# radio.net
KiCad netlist of a schematic drawn in Altium Designer
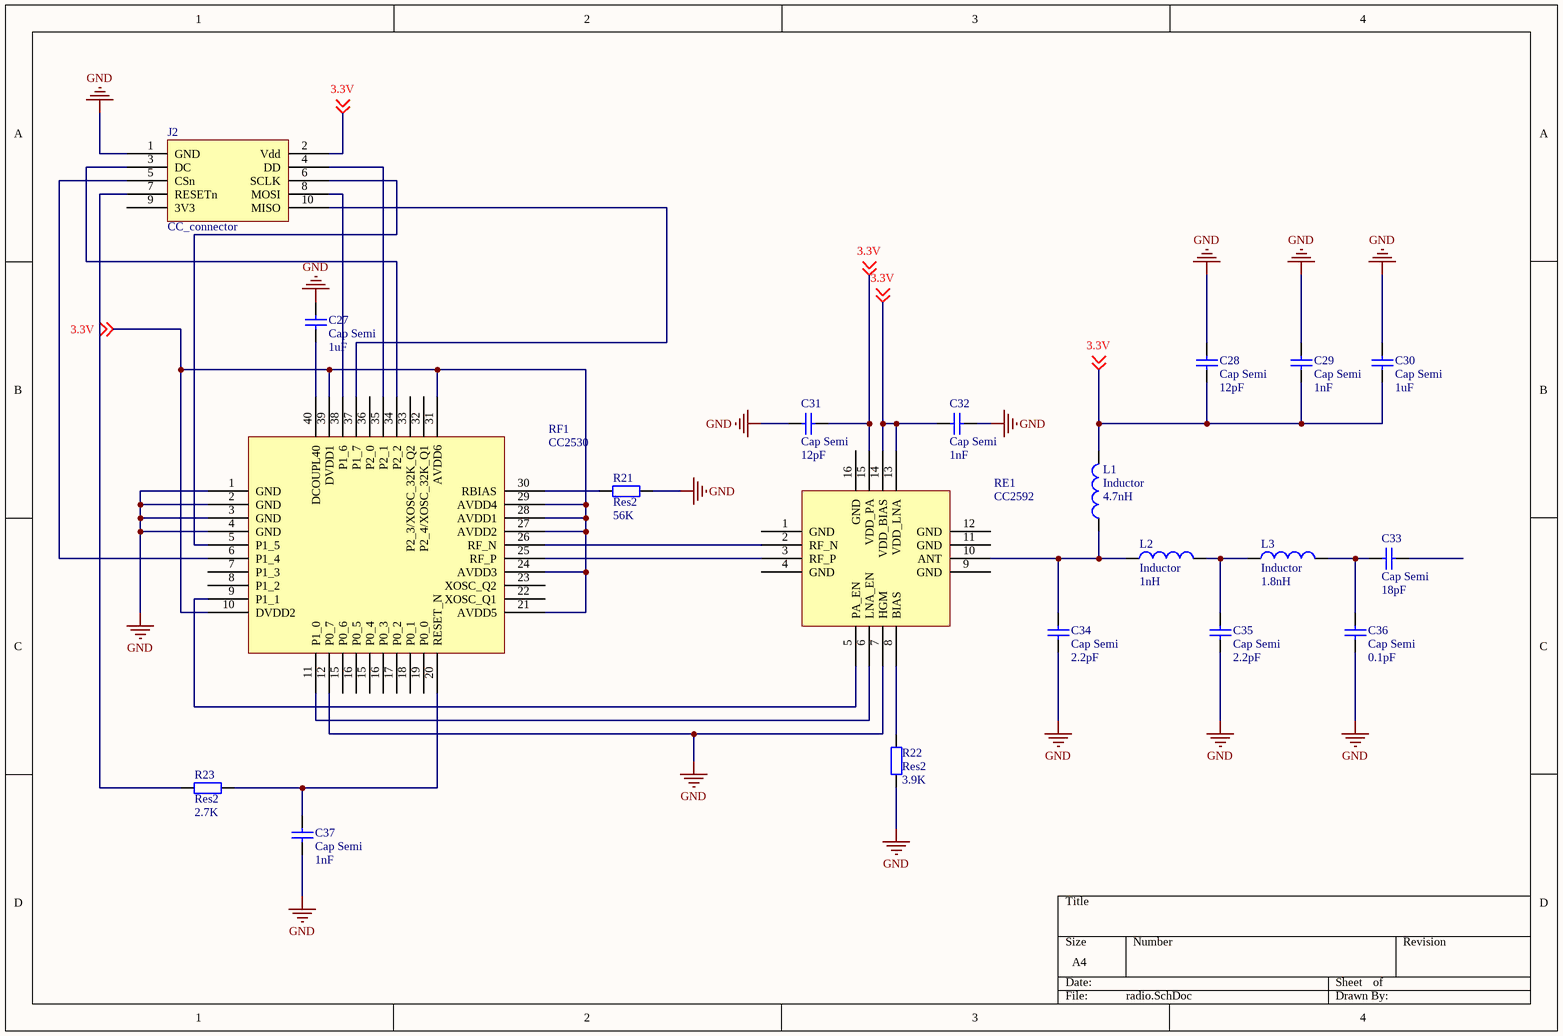
[diagram p0: radio.SchDoc]

(export (version "E")
  (design (tool "Eeschema 10.0.6"))
  (components
    (comp (ref "C27")
      (value "Cap Semi")
      (footprint "C1206")
      (description "Capacitor (Semiconductor SIM Model)")
      (fields (field (name "ALTIUM_VALUE") "1uF") (field (name "PUBLISHER") "Altium Limited"))
      (libsource (lib "Miscellaneous Devices") (part "Cap Semi"))
    )
    (comp (ref "C28")
      (value "Cap Semi")
      (footprint "C1206")
      (description "Capacitor (Semiconductor SIM Model)")
      (fields (field (name "ALTIUM_VALUE") "12pF") (field (name "PUBLISHER") "Altium Limited"))
      (libsource (lib "Miscellaneous Devices") (part "Cap Semi"))
    )
    (comp (ref "C29")
      (value "Cap Semi")
      (footprint "C1206")
      (description "Capacitor (Semiconductor SIM Model)")
      (fields (field (name "ALTIUM_VALUE") "1nF") (field (name "PUBLISHER") "Altium Limited"))
      (libsource (lib "Miscellaneous Devices") (part "Cap Semi"))
    )
    (comp (ref "C30")
      (value "Cap Semi")
      (footprint "C1206")
      (description "Capacitor (Semiconductor SIM Model)")
      (fields (field (name "ALTIUM_VALUE") "1uF") (field (name "PUBLISHER") "Altium Limited"))
      (libsource (lib "Miscellaneous Devices") (part "Cap Semi"))
    )
    (comp (ref "C31")
      (value "Cap Semi")
      (footprint "C1206")
      (description "Capacitor (Semiconductor SIM Model)")
      (fields (field (name "ALTIUM_VALUE") "12pF") (field (name "PUBLISHER") "Altium Limited"))
      (libsource (lib "Miscellaneous Devices") (part "Cap Semi"))
    )
    (comp (ref "C32")
      (value "Cap Semi")
      (footprint "C1206")
      (description "Capacitor (Semiconductor SIM Model)")
      (fields (field (name "ALTIUM_VALUE") "1nF") (field (name "PUBLISHER") "Altium Limited"))
      (libsource (lib "Miscellaneous Devices") (part "Cap Semi"))
    )
    (comp (ref "C33")
      (value "Cap Semi")
      (footprint "C1206")
      (description "Capacitor (Semiconductor SIM Model)")
      (fields (field (name "ALTIUM_VALUE") "18pF") (field (name "PUBLISHER") "Altium Limited"))
      (libsource (lib "Miscellaneous Devices") (part "Cap Semi"))
    )
    (comp (ref "C34")
      (value "Cap Semi")
      (footprint "C1206")
      (description "Capacitor (Semiconductor SIM Model)")
      (fields (field (name "ALTIUM_VALUE") "2.2pF") (field (name "PUBLISHER") "Altium Limited"))
      (libsource (lib "Miscellaneous Devices") (part "Cap Semi"))
    )
    (comp (ref "C35")
      (value "Cap Semi")
      (footprint "C1206")
      (description "Capacitor (Semiconductor SIM Model)")
      (fields (field (name "ALTIUM_VALUE") "2.2pF") (field (name "PUBLISHER") "Altium Limited"))
      (libsource (lib "Miscellaneous Devices") (part "Cap Semi"))
    )
    (comp (ref "C36")
      (value "Cap Semi")
      (footprint "C1206")
      (description "Capacitor (Semiconductor SIM Model)")
      (fields (field (name "ALTIUM_VALUE") "0.1pF") (field (name "PUBLISHER") "Altium Limited"))
      (libsource (lib "Miscellaneous Devices") (part "Cap Semi"))
    )
    (comp (ref "C37")
      (value "Cap Semi")
      (footprint "C1206")
      (description "Capacitor (Semiconductor SIM Model)")
      (fields (field (name "ALTIUM_VALUE") "1nF") (field (name "PUBLISHER") "Altium Limited"))
      (libsource (lib "Miscellaneous Devices") (part "Cap Semi"))
    )
    (comp (ref "J2")
      (value "CC_connector")
      (description "CC Debugger TI connector")
      (libsource (lib "components") (part "CC_connector"))
    )
    (comp (ref "L1")
      (value "Inductor")
      (footprint "0402-A")
      (fields (field (name "ALTIUM_VALUE") "4.7nH") (field (name "PUBLISHER") "Altium Limited"))
      (libsource (lib "Miscellaneous Devices") (part "Inductor"))
    )
    (comp (ref "L2")
      (value "Inductor")
      (footprint "0402-A")
      (fields (field (name "ALTIUM_VALUE") "1nH") (field (name "PUBLISHER") "Altium Limited"))
      (libsource (lib "Miscellaneous Devices") (part "Inductor"))
    )
    (comp (ref "L3")
      (value "Inductor")
      (footprint "0402-A")
      (fields (field (name "ALTIUM_VALUE") "1.8nH") (field (name "PUBLISHER") "Altium Limited"))
      (libsource (lib "Miscellaneous Devices") (part "Inductor"))
    )
    (comp (ref "R21")
      (value "Res2")
      (footprint "AXIAL-0.4")
      (description "Resistor")
      (fields (field (name "ALTIUM_VALUE") "56K") (field (name "PUBLISHER") "Altium Limited"))
      (libsource (lib "Miscellaneous Devices") (part "Res2"))
    )
    (comp (ref "R22")
      (value "Res2")
      (footprint "AXIAL-0.4")
      (description "Resistor")
      (fields (field (name "ALTIUM_VALUE") "3.9K") (field (name "PUBLISHER") "Altium Limited"))
      (libsource (lib "") (part "Res2_1"))
    )
    (comp (ref "R23")
      (value "Res2")
      (footprint "AXIAL-0.4")
      (description "Resistor")
      (fields (field (name "ALTIUM_VALUE") "2.7K") (field (name "PUBLISHER") "Altium Limited"))
      (libsource (lib "Miscellaneous Devices") (part "Res2"))
    )
    (comp (ref "RE1")
      (value "CC2592")
      (description "Range Extender 2.5GHz")
      (libsource (lib "components") (part "CC2592"))
    )
    (comp (ref "RF1")
      (value "CC2530")
      (description "RF 2.5GHz module")
      (libsource (lib "components") (part "CC2530"))
    )
  )
  (nets
    (net (code "1") (name "3.3V") (class "Default")
      (node (ref "C28") (pin "1") (pinfunction "1_1") (pintype "passive"))
      (node (ref "C29") (pin "1") (pinfunction "1_1") (pintype "passive"))
      (node (ref "C30") (pin "1") (pinfunction "1_1") (pintype "passive"))
      (node (ref "C31") (pin "2") (pinfunction "2_2") (pintype "passive"))
      (node (ref "C32") (pin "1") (pinfunction "1_1") (pintype "passive"))
      (node (ref "J2") (pin "2") (pinfunction "Vdd_2") (pintype "passive"))
      (node (ref "L1") (pin "2") (pinfunction "2_2") (pintype "passive"))
      (node (ref "RE1") (pin "13") (pinfunction "VDD_LNA_13") (pintype "passive"))
      (node (ref "RE1") (pin "14") (pinfunction "VDD_BIAS_14") (pintype "passive"))
      (node (ref "RE1") (pin "15") (pinfunction "VDD_PA_15") (pintype "passive"))
      (node (ref "RF1") (pin "10") (pinfunction "DVDD2_10") (pintype "passive"))
      (node (ref "RF1") (pin "21") (pinfunction "AVDD5_21") (pintype "passive"))
      (node (ref "RF1") (pin "24") (pinfunction "AVDD3_24") (pintype "passive"))
      (node (ref "RF1") (pin "27") (pinfunction "AVDD2_27") (pintype "passive"))
      (node (ref "RF1") (pin "28") (pinfunction "AVDD1_28") (pintype "passive"))
      (node (ref "RF1") (pin "29") (pinfunction "AVDD4_29") (pintype "passive"))
      (node (ref "RF1") (pin "31") (pinfunction "AVDD6_31") (pintype "passive"))
      (node (ref "RF1") (pin "39") (pinfunction "DVDD1_39") (pintype "passive"))
    )
    (net (code "2") (name "GND") (class "Default")
      (node (ref "C27") (pin "1") (pinfunction "1_1") (pintype "passive"))
      (node (ref "C28") (pin "2") (pinfunction "2_2") (pintype "passive"))
      (node (ref "C29") (pin "2") (pinfunction "2_2") (pintype "passive"))
      (node (ref "C30") (pin "2") (pinfunction "2_2") (pintype "passive"))
      (node (ref "C31") (pin "1") (pinfunction "1_1") (pintype "passive"))
      (node (ref "C32") (pin "2") (pinfunction "2_2") (pintype "passive"))
      (node (ref "C34") (pin "1") (pinfunction "1_1") (pintype "passive"))
      (node (ref "C35") (pin "1") (pinfunction "1_1") (pintype "passive"))
      (node (ref "C36") (pin "1") (pinfunction "1_1") (pintype "passive"))
      (node (ref "C37") (pin "1") (pinfunction "1_1") (pintype "passive"))
      (node (ref "J2") (pin "1") (pinfunction "GND_1") (pintype "passive"))
      (node (ref "R21") (pin "1") (pinfunction "1_1") (pintype "passive"))
      (node (ref "R22") (pin "2") (pinfunction "2_2") (pintype "passive"))
      (node (ref "RE1") (pin "7") (pinfunction "HGM_7") (pintype "passive"))
      (node (ref "RF1") (pin "1") (pinfunction "GND_1") (pintype "passive"))
      (node (ref "RF1") (pin "12") (pinfunction "P0_7_12") (pintype "passive"))
      (node (ref "RF1") (pin "2") (pinfunction "GND_2") (pintype "passive"))
      (node (ref "RF1") (pin "3") (pinfunction "GND_3") (pintype "passive"))
      (node (ref "RF1") (pin "4") (pinfunction "GND_4") (pintype "passive"))
    )
    (net (code "3") (name "Net-(C33-Pad1)") (class "Default")
      (node (ref "C33") (pin "1") (pinfunction "1_1") (pintype "passive"))
      (node (ref "C36") (pin "2") (pinfunction "2_2") (pintype "passive"))
      (node (ref "L3") (pin "2") (pinfunction "2_2") (pintype "passive"))
    )
    (net (code "4") (name "Net-(C35-Pad2)") (class "Default")
      (node (ref "C35") (pin "2") (pinfunction "2_2") (pintype "passive"))
      (node (ref "L2") (pin "2") (pinfunction "2_2") (pintype "passive"))
      (node (ref "L3") (pin "1") (pinfunction "1_1") (pintype "passive"))
    )
    (net (code "5") (name "Net-(J2-CSn)") (class "Default")
      (node (ref "J2") (pin "5") (pinfunction "CSn_5") (pintype "passive"))
      (node (ref "RF1") (pin "6") (pinfunction "P1_4_6") (pintype "passive"))
    )
    (net (code "6") (name "Net-(J2-DC)") (class "Default")
      (node (ref "J2") (pin "3") (pinfunction "DC_3") (pintype "passive"))
      (node (ref "RF1") (pin "34") (pinfunction "P2_2_34") (pintype "passive"))
    )
    (net (code "7") (name "Net-(J2-DD)") (class "Default")
      (node (ref "J2") (pin "4") (pinfunction "DD_4") (pintype "passive"))
      (node (ref "RF1") (pin "35") (pinfunction "P2_1_35") (pintype "passive"))
    )
    (net (code "8") (name "Net-(J2-MISO)") (class "Default")
      (node (ref "J2") (pin "10") (pinfunction "MISO_10") (pintype "passive"))
      (node (ref "RF1") (pin "37") (pinfunction "P1_7_37") (pintype "passive"))
    )
    (net (code "9") (name "Net-(J2-MOSI)") (class "Default")
      (node (ref "J2") (pin "8") (pinfunction "MOSI_8") (pintype "passive"))
      (node (ref "RF1") (pin "38") (pinfunction "P1_6_38") (pintype "passive"))
    )
    (net (code "10") (name "Net-(J2-RESETn)") (class "Default")
      (node (ref "J2") (pin "7") (pinfunction "RESETn_7") (pintype "passive"))
      (node (ref "R23") (pin "2") (pinfunction "2_2") (pintype "passive"))
    )
    (net (code "11") (name "Net-(J2-SCLK)") (class "Default")
      (node (ref "J2") (pin "6") (pinfunction "SCLK_6") (pintype "passive"))
      (node (ref "RF1") (pin "5") (pinfunction "P1_5_5") (pintype "passive"))
    )
    (net (code "12") (name "Net-(RE1-ANT)") (class "Default")
      (node (ref "C34") (pin "2") (pinfunction "2_2") (pintype "passive"))
      (node (ref "L1") (pin "1") (pinfunction "1_1") (pintype "passive"))
      (node (ref "L2") (pin "1") (pinfunction "1_1") (pintype "passive"))
      (node (ref "RE1") (pin "10") (pinfunction "ANT_10") (pintype "passive"))
    )
    (net (code "13") (name "Net-(RE1-BIAS)") (class "Default")
      (node (ref "R22") (pin "1") (pinfunction "1_1") (pintype "passive"))
      (node (ref "RE1") (pin "8") (pinfunction "BIAS_8") (pintype "passive"))
    )
    (net (code "14") (name "Net-(RE1-LNA_EN)") (class "Default")
      (node (ref "RE1") (pin "6") (pinfunction "LNA_EN_6") (pintype "passive"))
      (node (ref "RF1") (pin "11") (pinfunction "P1_0_11") (pintype "passive"))
    )
    (net (code "15") (name "Net-(RE1-PA_EN)") (class "Default")
      (node (ref "RE1") (pin "5") (pinfunction "PA_EN_5") (pintype "passive"))
      (node (ref "RF1") (pin "9") (pinfunction "P1_1_9") (pintype "passive"))
    )
    (net (code "16") (name "Net-(RE1-RF_N)") (class "Default")
      (node (ref "RE1") (pin "2") (pinfunction "RF_N_2") (pintype "passive"))
      (node (ref "RF1") (pin "26") (pinfunction "RF_N_26") (pintype "passive"))
    )
    (net (code "17") (name "Net-(RE1-RF_P)") (class "Default")
      (node (ref "RE1") (pin "3") (pinfunction "RF_P_3") (pintype "passive"))
      (node (ref "RF1") (pin "25") (pinfunction "RF_P_25") (pintype "passive"))
    )
    (net (code "18") (name "Net-(RF1-DCOUPL40)") (class "Default")
      (node (ref "C27") (pin "2") (pinfunction "2_2") (pintype "passive"))
      (node (ref "RF1") (pin "40") (pinfunction "DCOUPL40_40") (pintype "passive"))
    )
    (net (code "19") (name "Net-(RF1-RBIAS)") (class "Default")
      (node (ref "R21") (pin "2") (pinfunction "2_2") (pintype "passive"))
      (node (ref "RF1") (pin "30") (pinfunction "RBIAS_30") (pintype "passive"))
    )
    (net (code "20") (name "Net-(RF1-RESET_N)") (class "Default")
      (node (ref "C37") (pin "2") (pinfunction "2_2") (pintype "passive"))
      (node (ref "R23") (pin "1") (pinfunction "1_1") (pintype "passive"))
      (node (ref "RF1") (pin "20") (pinfunction "RESET_N_20") (pintype "passive"))
    )
    (net (code "21") (name "unconnected-(C33-Pad2)") (class "Default")
      (node (ref "C33") (pin "2") (pinfunction "2_2") (pintype "passive"))
    )
    (net (code "22") (name "unconnected-(J2-3V3-Pad9)") (class "Default")
      (node (ref "J2") (pin "9") (pinfunction "3V3_9") (pintype "passive"))
    )
    (net (code "23") (name "unconnected-(RE1-GND-Pad1)") (class "Default")
      (node (ref "RE1") (pin "1") (pinfunction "GND_1") (pintype "passive"))
    )
    (net (code "24") (name "unconnected-(RE1-GND-Pad4)") (class "Default")
      (node (ref "RE1") (pin "4") (pinfunction "GND_4") (pintype "passive"))
    )
    (net (code "25") (name "unconnected-(RE1-GND-Pad9)") (class "Default")
      (node (ref "RE1") (pin "9") (pinfunction "GND_9") (pintype "passive"))
    )
    (net (code "26") (name "unconnected-(RE1-GND-Pad11)") (class "Default")
      (node (ref "RE1") (pin "11") (pinfunction "GND_11") (pintype "passive"))
    )
    (net (code "27") (name "unconnected-(RE1-GND-Pad12)") (class "Default")
      (node (ref "RE1") (pin "12") (pinfunction "GND_12") (pintype "passive"))
    )
    (net (code "28") (name "unconnected-(RE1-GND-Pad16)") (class "Default")
      (node (ref "RE1") (pin "16") (pinfunction "GND_16") (pintype "passive"))
    )
    (net (code "29") (name "unconnected-(RF1-P0_0-Pad19)") (class "Default")
      (node (ref "RF1") (pin "19") (pinfunction "P0_0_19") (pintype "passive"))
    )
    (net (code "30") (name "unconnected-(RF1-P0_1-Pad18)") (class "Default")
      (node (ref "RF1") (pin "18") (pinfunction "P0_1_18") (pintype "passive"))
    )
    (net (code "31") (name "unconnected-(RF1-P0_2-Pad17)") (class "Default")
      (node (ref "RF1") (pin "17") (pinfunction "P0_2_17") (pintype "passive"))
    )
    (net (code "32") (name "unconnected-(RF1-P0_3-Pad16)") (class "Default")
      (node (ref "RF1") (pin "16") (pinfunction "P0_3_16") (pintype "passive"))
    )
    (net (code "33") (name "unconnected-(RF1-P0_4-Pad15)") (class "Default")
      (node (ref "RF1") (pin "15") (pinfunction "P0_4_15") (pintype "passive"))
    )
    (net (code "34") (name "unconnected-(RF1-P0_5-Pad16)") (class "Default")
      (node (ref "RF1") (pin "16") (pinfunction "P0_5_16") (pintype "passive"))
    )
    (net (code "35") (name "unconnected-(RF1-P0_6-Pad15)") (class "Default")
      (node (ref "RF1") (pin "15") (pinfunction "P0_6_15") (pintype "passive"))
    )
    (net (code "36") (name "unconnected-(RF1-P1_2-Pad8)") (class "Default")
      (node (ref "RF1") (pin "8") (pinfunction "P1_2_8") (pintype "passive"))
    )
    (net (code "37") (name "unconnected-(RF1-P1_3-Pad7)") (class "Default")
      (node (ref "RF1") (pin "7") (pinfunction "P1_3_7") (pintype "passive"))
    )
    (net (code "38") (name "unconnected-(RF1-P2_0-Pad36)") (class "Default")
      (node (ref "RF1") (pin "36") (pinfunction "P2_0_36") (pintype "passive"))
    )
    (net (code "39") (name "unconnected-(RF1-P2_3{slash}XOSC_32K_Q2-Pad33)") (class "Default")
      (node (ref "RF1") (pin "33") (pinfunction "P2_3/XOSC_32K_Q2_33") (pintype "passive"))
    )
    (net (code "40") (name "unconnected-(RF1-P2_4{slash}XOSC_32K_Q1-Pad32)") (class "Default")
      (node (ref "RF1") (pin "32") (pinfunction "P2_4/XOSC_32K_Q1_32") (pintype "passive"))
    )
    (net (code "41") (name "unconnected-(RF1-XOSC_Q1-Pad22)") (class "Default")
      (node (ref "RF1") (pin "22") (pinfunction "XOSC_Q1_22") (pintype "passive"))
    )
    (net (code "42") (name "unconnected-(RF1-XOSC_Q2-Pad23)") (class "Default")
      (node (ref "RF1") (pin "23") (pinfunction "XOSC_Q2_23") (pintype "passive"))
    )
  )
)
